# tick-mk-5_0.net
KiCad netlist of a schematic drawn in EAGLE
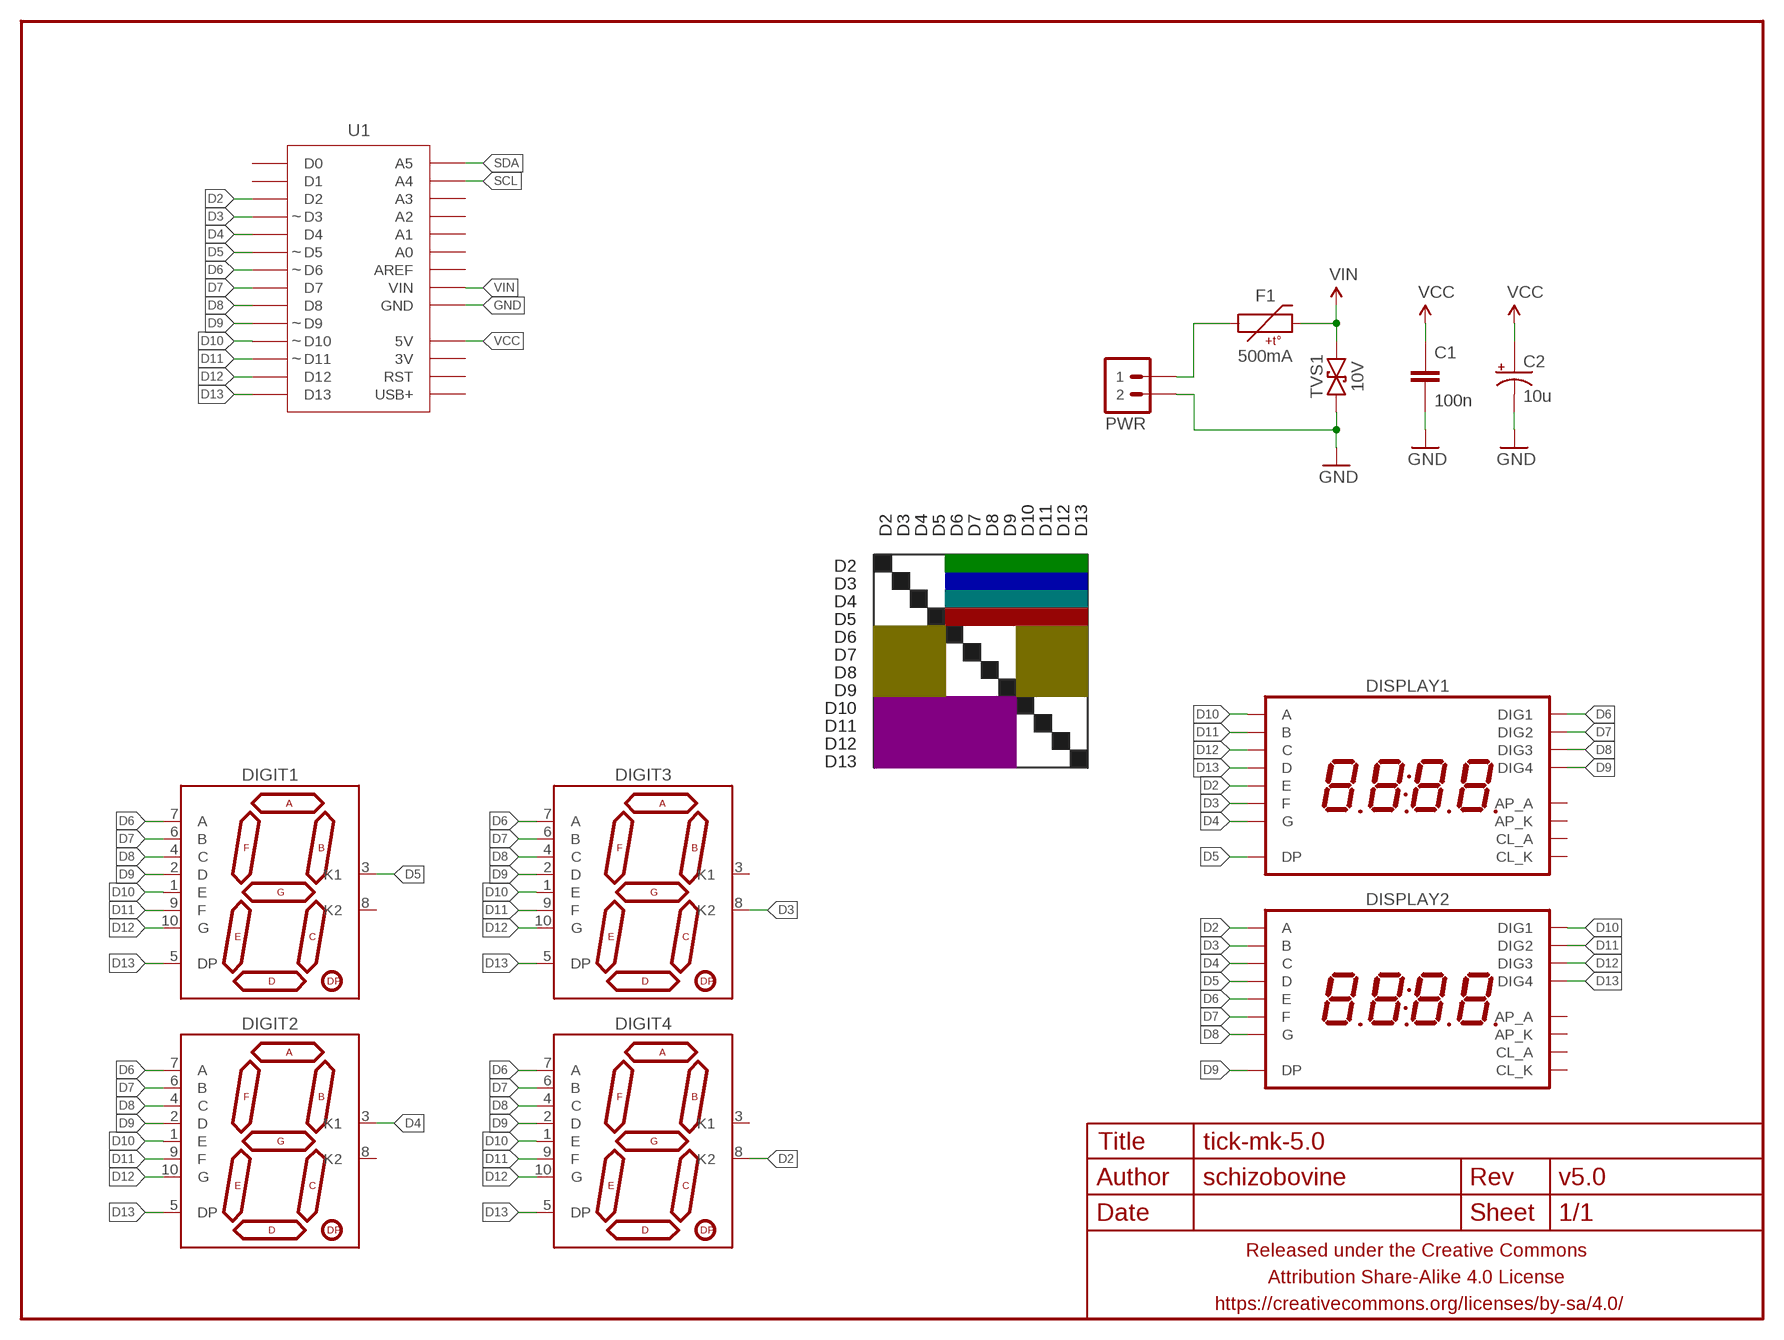
[diagram p0: schematic, sheet 1]

(export (version "E")
  (design (tool "Eeschema 10.0.6"))
  (components
    (comp (ref "C1")
      (value "100n")
      (footprint "eagle-import:C025-024X044")
      (libsource (lib "eagle-import") (part "CAPACITOR-CERAMIC025-024X044"))
    )
    (comp (ref "C2")
      (value "10u")
      (footprint "eagle-import:E2-5")
      (libsource (lib "eagle-import") (part "CAPACITOR-POLARIZEDE2-5"))
    )
    (comp (ref "DIGIT1")
      (value "7SEG_1DIGPTH-25.4MM-BARE")
      (footprint "eagle-import:7SEG_1DIG_25.4MM_NOSILK")
      (libsource (lib "eagle-import") (part "7SEG_1DIGPTH-25.4MM-BARE"))
    )
    (comp (ref "DIGIT2")
      (value "7SEG_1DIGPTH-25.4MM-BARE")
      (footprint "eagle-import:7SEG_1DIG_25.4MM_NOSILK")
      (libsource (lib "eagle-import") (part "7SEG_1DIGPTH-25.4MM-BARE"))
    )
    (comp (ref "DIGIT3")
      (value "7SEG_1DIGPTH-25.4MM-BARE")
      (footprint "eagle-import:7SEG_1DIG_25.4MM_NOSILK")
      (libsource (lib "eagle-import") (part "7SEG_1DIGPTH-25.4MM-BARE"))
    )
    (comp (ref "DIGIT4")
      (value "7SEG_1DIGPTH-25.4MM-BARE")
      (footprint "eagle-import:7SEG_1DIG_25.4MM_NOSILK")
      (libsource (lib "eagle-import") (part "7SEG_1DIGPTH-25.4MM-BARE"))
    )
    (comp (ref "DISPLAY1")
      (value "7SEG_4DIGIT_COLON_APOS")
      (footprint "eagle-import:7SEG_4DIG_10MM")
      (libsource (lib "eagle-import") (part "7SEG_4DIGIT_COLON_APOS"))
    )
    (comp (ref "DISPLAY2")
      (value "7SEG_4DIGIT_COLON_APOS")
      (footprint "eagle-import:7SEG_4DIG_10MM")
      (libsource (lib "eagle-import") (part "7SEG_4DIGIT_COLON_APOS"))
    )
    (comp (ref "F1")
      (value "500mA")
      (footprint "eagle-import:PTC-PTH-5.08MM")
      (libsource (lib "eagle-import") (part "PTCPTH-5.08MM"))
    )
    (comp (ref "FRAME1")
      (value "FRAME-LETTERNO_PACKAGE")
      (footprint "eagle-import:DUMMY")
      (fields (field (name "DESIGNER") "schizobovine") (field (name "VERSION") "v5.0"))
      (libsource (lib "eagle-import") (part "FRAME-LETTERNO_PACKAGE"))
    )
    (comp (ref "PWR")
      (value "M02JST-PTH-VERT")
      (footprint "eagle-import:JST-2-PH-VERT-PTH")
      (libsource (lib "eagle-import") (part "M02JST-PTH-VERT"))
    )
    (comp (ref "TVS1")
      (value "10V")
      (footprint "eagle-import:DO-41-TVS-BI-10.16MM")
      (libsource (lib "eagle-import") (part "TVSDO-41-10.16MM"))
    )
    (comp (ref "U1")
      (value "ADAFRUIT_METRO_MININOHOLES-NOOUTLINE-SILK")
      (footprint "eagle-import:ADAFRUIT_METRO_MINI")
      (libsource (lib "eagle-import") (part "ADAFRUIT_METRO_MININOHOLES-NOOUTLINE-SILK"))
    )
  )
  (nets
    (net (code "1") (name "D2") (class "Default")
      (node (ref "DIGIT4") (pin "8") (pinfunction "K2_8") (pintype "bidirectional"))
      (node (ref "DISPLAY1") (pin "5") (pinfunction "E_5") (pintype "passive"))
      (node (ref "DISPLAY2") (pin "14") (pinfunction "A_14") (pintype "passive"))
      (node (ref "U1") (pin "3") (pinfunction "D2_3") (pintype "bidirectional"))
    )
    (net (code "2") (name "D3") (class "Default")
      (node (ref "DIGIT3") (pin "8") (pinfunction "K2_8") (pintype "bidirectional"))
      (node (ref "DISPLAY1") (pin "11") (pinfunction "F_11") (pintype "passive"))
      (node (ref "DISPLAY2") (pin "16") (pinfunction "B_16") (pintype "passive"))
      (node (ref "U1") (pin "4") (pinfunction "D3_4") (pintype "bidirectional"))
    )
    (net (code "3") (name "D4") (class "Default")
      (node (ref "DIGIT2") (pin "3") (pinfunction "K1_3") (pintype "bidirectional"))
      (node (ref "DISPLAY1") (pin "15") (pinfunction "G_15") (pintype "passive"))
      (node (ref "DISPLAY2") (pin "13") (pinfunction "C_13") (pintype "passive"))
      (node (ref "U1") (pin "5") (pinfunction "D4_5") (pintype "bidirectional"))
    )
    (net (code "4") (name "D5") (class "Default")
      (node (ref "DIGIT1") (pin "3") (pinfunction "K1_3") (pintype "bidirectional"))
      (node (ref "DISPLAY1") (pin "7") (pinfunction "DP_7") (pintype "passive"))
      (node (ref "DISPLAY2") (pin "3") (pinfunction "D_3") (pintype "passive"))
      (node (ref "U1") (pin "6") (pinfunction "D5_6") (pintype "bidirectional"))
    )
    (net (code "5") (name "D6") (class "Default")
      (node (ref "DIGIT1") (pin "7") (pinfunction "A_7") (pintype "bidirectional"))
      (node (ref "DIGIT2") (pin "7") (pinfunction "A_7") (pintype "bidirectional"))
      (node (ref "DIGIT3") (pin "7") (pinfunction "A_7") (pintype "bidirectional"))
      (node (ref "DIGIT4") (pin "7") (pinfunction "A_7") (pintype "bidirectional"))
      (node (ref "DISPLAY1") (pin "1") (pinfunction "DIG1_1") (pintype "passive"))
      (node (ref "DISPLAY2") (pin "5") (pinfunction "E_5") (pintype "passive"))
      (node (ref "U1") (pin "7") (pinfunction "D6_7") (pintype "bidirectional"))
    )
    (net (code "6") (name "D7") (class "Default")
      (node (ref "DIGIT1") (pin "6") (pinfunction "B_6") (pintype "bidirectional"))
      (node (ref "DIGIT2") (pin "6") (pinfunction "B_6") (pintype "bidirectional"))
      (node (ref "DIGIT3") (pin "6") (pinfunction "B_6") (pintype "bidirectional"))
      (node (ref "DIGIT4") (pin "6") (pinfunction "B_6") (pintype "bidirectional"))
      (node (ref "DISPLAY1") (pin "2") (pinfunction "DIG2_2") (pintype "passive"))
      (node (ref "DISPLAY2") (pin "11") (pinfunction "F_11") (pintype "passive"))
      (node (ref "U1") (pin "8") (pinfunction "D7_8") (pintype "bidirectional"))
    )
    (net (code "7") (name "D8") (class "Default")
      (node (ref "DIGIT1") (pin "4") (pinfunction "C_4") (pintype "bidirectional"))
      (node (ref "DIGIT2") (pin "4") (pinfunction "C_4") (pintype "bidirectional"))
      (node (ref "DIGIT3") (pin "4") (pinfunction "C_4") (pintype "bidirectional"))
      (node (ref "DIGIT4") (pin "4") (pinfunction "C_4") (pintype "bidirectional"))
      (node (ref "DISPLAY1") (pin "6") (pinfunction "DIG3_6") (pintype "passive"))
      (node (ref "DISPLAY2") (pin "15") (pinfunction "G_15") (pintype "passive"))
      (node (ref "U1") (pin "9") (pinfunction "D8_9") (pintype "bidirectional"))
    )
    (net (code "8") (name "D9") (class "Default")
      (node (ref "DIGIT1") (pin "2") (pinfunction "D_2") (pintype "bidirectional"))
      (node (ref "DIGIT2") (pin "2") (pinfunction "D_2") (pintype "bidirectional"))
      (node (ref "DIGIT3") (pin "2") (pinfunction "D_2") (pintype "bidirectional"))
      (node (ref "DIGIT4") (pin "2") (pinfunction "D_2") (pintype "bidirectional"))
      (node (ref "DISPLAY1") (pin "8") (pinfunction "DIG4_8") (pintype "passive"))
      (node (ref "DISPLAY2") (pin "7") (pinfunction "DP_7") (pintype "passive"))
      (node (ref "U1") (pin "10") (pinfunction "D9_10") (pintype "bidirectional"))
    )
    (net (code "9") (name "D10") (class "Default")
      (node (ref "DIGIT1") (pin "1") (pinfunction "E_1") (pintype "bidirectional"))
      (node (ref "DIGIT2") (pin "1") (pinfunction "E_1") (pintype "bidirectional"))
      (node (ref "DIGIT3") (pin "1") (pinfunction "E_1") (pintype "bidirectional"))
      (node (ref "DIGIT4") (pin "1") (pinfunction "E_1") (pintype "bidirectional"))
      (node (ref "DISPLAY1") (pin "14") (pinfunction "A_14") (pintype "passive"))
      (node (ref "DISPLAY2") (pin "1") (pinfunction "DIG1_1") (pintype "passive"))
      (node (ref "U1") (pin "11") (pinfunction "D10_11") (pintype "bidirectional"))
    )
    (net (code "10") (name "D11") (class "Default")
      (node (ref "DIGIT1") (pin "9") (pinfunction "F_9") (pintype "bidirectional"))
      (node (ref "DIGIT2") (pin "9") (pinfunction "F_9") (pintype "bidirectional"))
      (node (ref "DIGIT3") (pin "9") (pinfunction "F_9") (pintype "bidirectional"))
      (node (ref "DIGIT4") (pin "9") (pinfunction "F_9") (pintype "bidirectional"))
      (node (ref "DISPLAY1") (pin "16") (pinfunction "B_16") (pintype "passive"))
      (node (ref "DISPLAY2") (pin "2") (pinfunction "DIG2_2") (pintype "passive"))
      (node (ref "U1") (pin "12") (pinfunction "D11_12") (pintype "bidirectional"))
    )
    (net (code "11") (name "D12") (class "Default")
      (node (ref "DIGIT1") (pin "10") (pinfunction "G_10") (pintype "bidirectional"))
      (node (ref "DIGIT2") (pin "10") (pinfunction "G_10") (pintype "bidirectional"))
      (node (ref "DIGIT3") (pin "10") (pinfunction "G_10") (pintype "bidirectional"))
      (node (ref "DIGIT4") (pin "10") (pinfunction "G_10") (pintype "bidirectional"))
      (node (ref "DISPLAY1") (pin "13") (pinfunction "C_13") (pintype "passive"))
      (node (ref "DISPLAY2") (pin "6") (pinfunction "DIG3_6") (pintype "passive"))
      (node (ref "U1") (pin "13") (pinfunction "D12_13") (pintype "bidirectional"))
    )
    (net (code "12") (name "D13") (class "Default")
      (node (ref "DIGIT1") (pin "5") (pinfunction "DP_5") (pintype "bidirectional"))
      (node (ref "DIGIT2") (pin "5") (pinfunction "DP_5") (pintype "bidirectional"))
      (node (ref "DIGIT3") (pin "5") (pinfunction "DP_5") (pintype "bidirectional"))
      (node (ref "DIGIT4") (pin "5") (pinfunction "DP_5") (pintype "bidirectional"))
      (node (ref "DISPLAY1") (pin "3") (pinfunction "D_3") (pintype "passive"))
      (node (ref "DISPLAY2") (pin "8") (pinfunction "DIG4_8") (pintype "passive"))
      (node (ref "U1") (pin "14") (pinfunction "D13_14") (pintype "bidirectional"))
    )
    (net (code "13") (name "GND") (class "Default")
      (node (ref "C1") (pin "2") (pinfunction "2_2") (pintype "passive"))
      (node (ref "C2") (pin "-") (pinfunction "-_-") (pintype "passive"))
      (node (ref "PWR") (pin "2") (pinfunction "2_2") (pintype "passive"))
      (node (ref "TVS1") (pin "P$1") (pinfunction "1_P$1") (pintype "passive"))
      (node (ref "U1") (pin "19") (pinfunction "GND_19") (pintype "bidirectional"))
      (node (ref "U1") (pin "20") (pinfunction "GND_20") (pintype "bidirectional"))
    )
    (net (code "14") (name "Net-(F1-1)") (class "Default")
      (node (ref "F1") (pin "P$1") (pinfunction "1_P$1") (pintype "passive"))
      (node (ref "PWR") (pin "1") (pinfunction "1_1") (pintype "passive"))
    )
    (net (code "15") (name "SCL") (class "Default")
      (node (ref "U1") (pin "27") (pinfunction "A4_27") (pintype "bidirectional"))
    )
    (net (code "16") (name "SDA") (class "Default")
      (node (ref "U1") (pin "28") (pinfunction "A5_28") (pintype "bidirectional"))
    )
    (net (code "17") (name "VCC") (class "Default")
      (node (ref "C1") (pin "1") (pinfunction "1_1") (pintype "passive"))
      (node (ref "C2") (pin "+") (pinfunction "+_+") (pintype "passive"))
      (node (ref "U1") (pin "18") (pinfunction "5V_18") (pintype "bidirectional"))
    )
    (net (code "18") (name "VIN") (class "Default")
      (node (ref "F1") (pin "P$2") (pinfunction "2_P$2") (pintype "passive"))
      (node (ref "TVS1") (pin "P$2") (pinfunction "2_P$2") (pintype "passive"))
      (node (ref "U1") (pin "21") (pinfunction "VIN_21") (pintype "bidirectional"))
    )
    (net (code "19") (name "unconnected-(DIGIT1-K2-Pad8)") (class "Default")
      (node (ref "DIGIT1") (pin "8") (pinfunction "K2_8") (pintype "bidirectional"))
    )
    (net (code "20") (name "unconnected-(DIGIT2-K2-Pad8)") (class "Default")
      (node (ref "DIGIT2") (pin "8") (pinfunction "K2_8") (pintype "bidirectional"))
    )
    (net (code "21") (name "unconnected-(DIGIT3-K1-Pad3)") (class "Default")
      (node (ref "DIGIT3") (pin "3") (pinfunction "K1_3") (pintype "bidirectional"))
    )
    (net (code "22") (name "unconnected-(DIGIT4-K1-Pad3)") (class "Default")
      (node (ref "DIGIT4") (pin "3") (pinfunction "K1_3") (pintype "bidirectional"))
    )
    (net (code "23") (name "unconnected-(DISPLAY1-AP_A-Pad10)") (class "Default")
      (node (ref "DISPLAY1") (pin "10") (pinfunction "AP_A_10") (pintype "bidirectional"))
    )
    (net (code "24") (name "unconnected-(DISPLAY1-AP_K-Pad9)") (class "Default")
      (node (ref "DISPLAY1") (pin "9") (pinfunction "AP_K_9") (pintype "bidirectional"))
    )
    (net (code "25") (name "unconnected-(DISPLAY1-CL_A-Pad4)") (class "Default")
      (node (ref "DISPLAY1") (pin "4") (pinfunction "CL_A_4") (pintype "passive"))
    )
    (net (code "26") (name "unconnected-(DISPLAY1-CL_K-Pad12)") (class "Default")
      (node (ref "DISPLAY1") (pin "12") (pinfunction "CL_K_12") (pintype "passive"))
    )
    (net (code "27") (name "unconnected-(DISPLAY2-AP_A-Pad10)") (class "Default")
      (node (ref "DISPLAY2") (pin "10") (pinfunction "AP_A_10") (pintype "bidirectional"))
    )
    (net (code "28") (name "unconnected-(DISPLAY2-AP_K-Pad9)") (class "Default")
      (node (ref "DISPLAY2") (pin "9") (pinfunction "AP_K_9") (pintype "bidirectional"))
    )
    (net (code "29") (name "unconnected-(DISPLAY2-CL_A-Pad4)") (class "Default")
      (node (ref "DISPLAY2") (pin "4") (pinfunction "CL_A_4") (pintype "passive"))
    )
    (net (code "30") (name "unconnected-(DISPLAY2-CL_K-Pad12)") (class "Default")
      (node (ref "DISPLAY2") (pin "12") (pinfunction "CL_K_12") (pintype "passive"))
    )
    (net (code "31") (name "unconnected-(U1-3V-Pad17)") (class "Default")
      (node (ref "U1") (pin "17") (pinfunction "3V_17") (pintype "bidirectional"))
    )
    (net (code "32") (name "unconnected-(U1-A0-Pad23)") (class "Default")
      (node (ref "U1") (pin "23") (pinfunction "A0_23") (pintype "bidirectional"))
    )
    (net (code "33") (name "unconnected-(U1-A1-Pad24)") (class "Default")
      (node (ref "U1") (pin "24") (pinfunction "A1_24") (pintype "bidirectional"))
    )
    (net (code "34") (name "unconnected-(U1-A2-Pad25)") (class "Default")
      (node (ref "U1") (pin "25") (pinfunction "A2_25") (pintype "bidirectional"))
    )
    (net (code "35") (name "unconnected-(U1-A3-Pad26)") (class "Default")
      (node (ref "U1") (pin "26") (pinfunction "A3_26") (pintype "bidirectional"))
    )
    (net (code "36") (name "unconnected-(U1-AREF-Pad22)") (class "Default")
      (node (ref "U1") (pin "22") (pinfunction "AREF_22") (pintype "bidirectional"))
    )
    (net (code "37") (name "unconnected-(U1-D0-Pad1)") (class "Default")
      (node (ref "U1") (pin "1") (pinfunction "D0_1") (pintype "bidirectional"))
    )
    (net (code "38") (name "unconnected-(U1-D1-Pad2)") (class "Default")
      (node (ref "U1") (pin "2") (pinfunction "D1_2") (pintype "bidirectional"))
    )
    (net (code "39") (name "unconnected-(U1-RST-Pad16)") (class "Default")
      (node (ref "U1") (pin "16") (pinfunction "RST_16") (pintype "bidirectional"))
    )
    (net (code "40") (name "unconnected-(U1-USB+-Pad15)") (class "Default")
      (node (ref "U1") (pin "15") (pinfunction "USB+_15") (pintype "bidirectional"))
    )
  )
)
